# AddOnBoardArduinoRTC.net
KiCad netlist of a schematic drawn in EAGLE
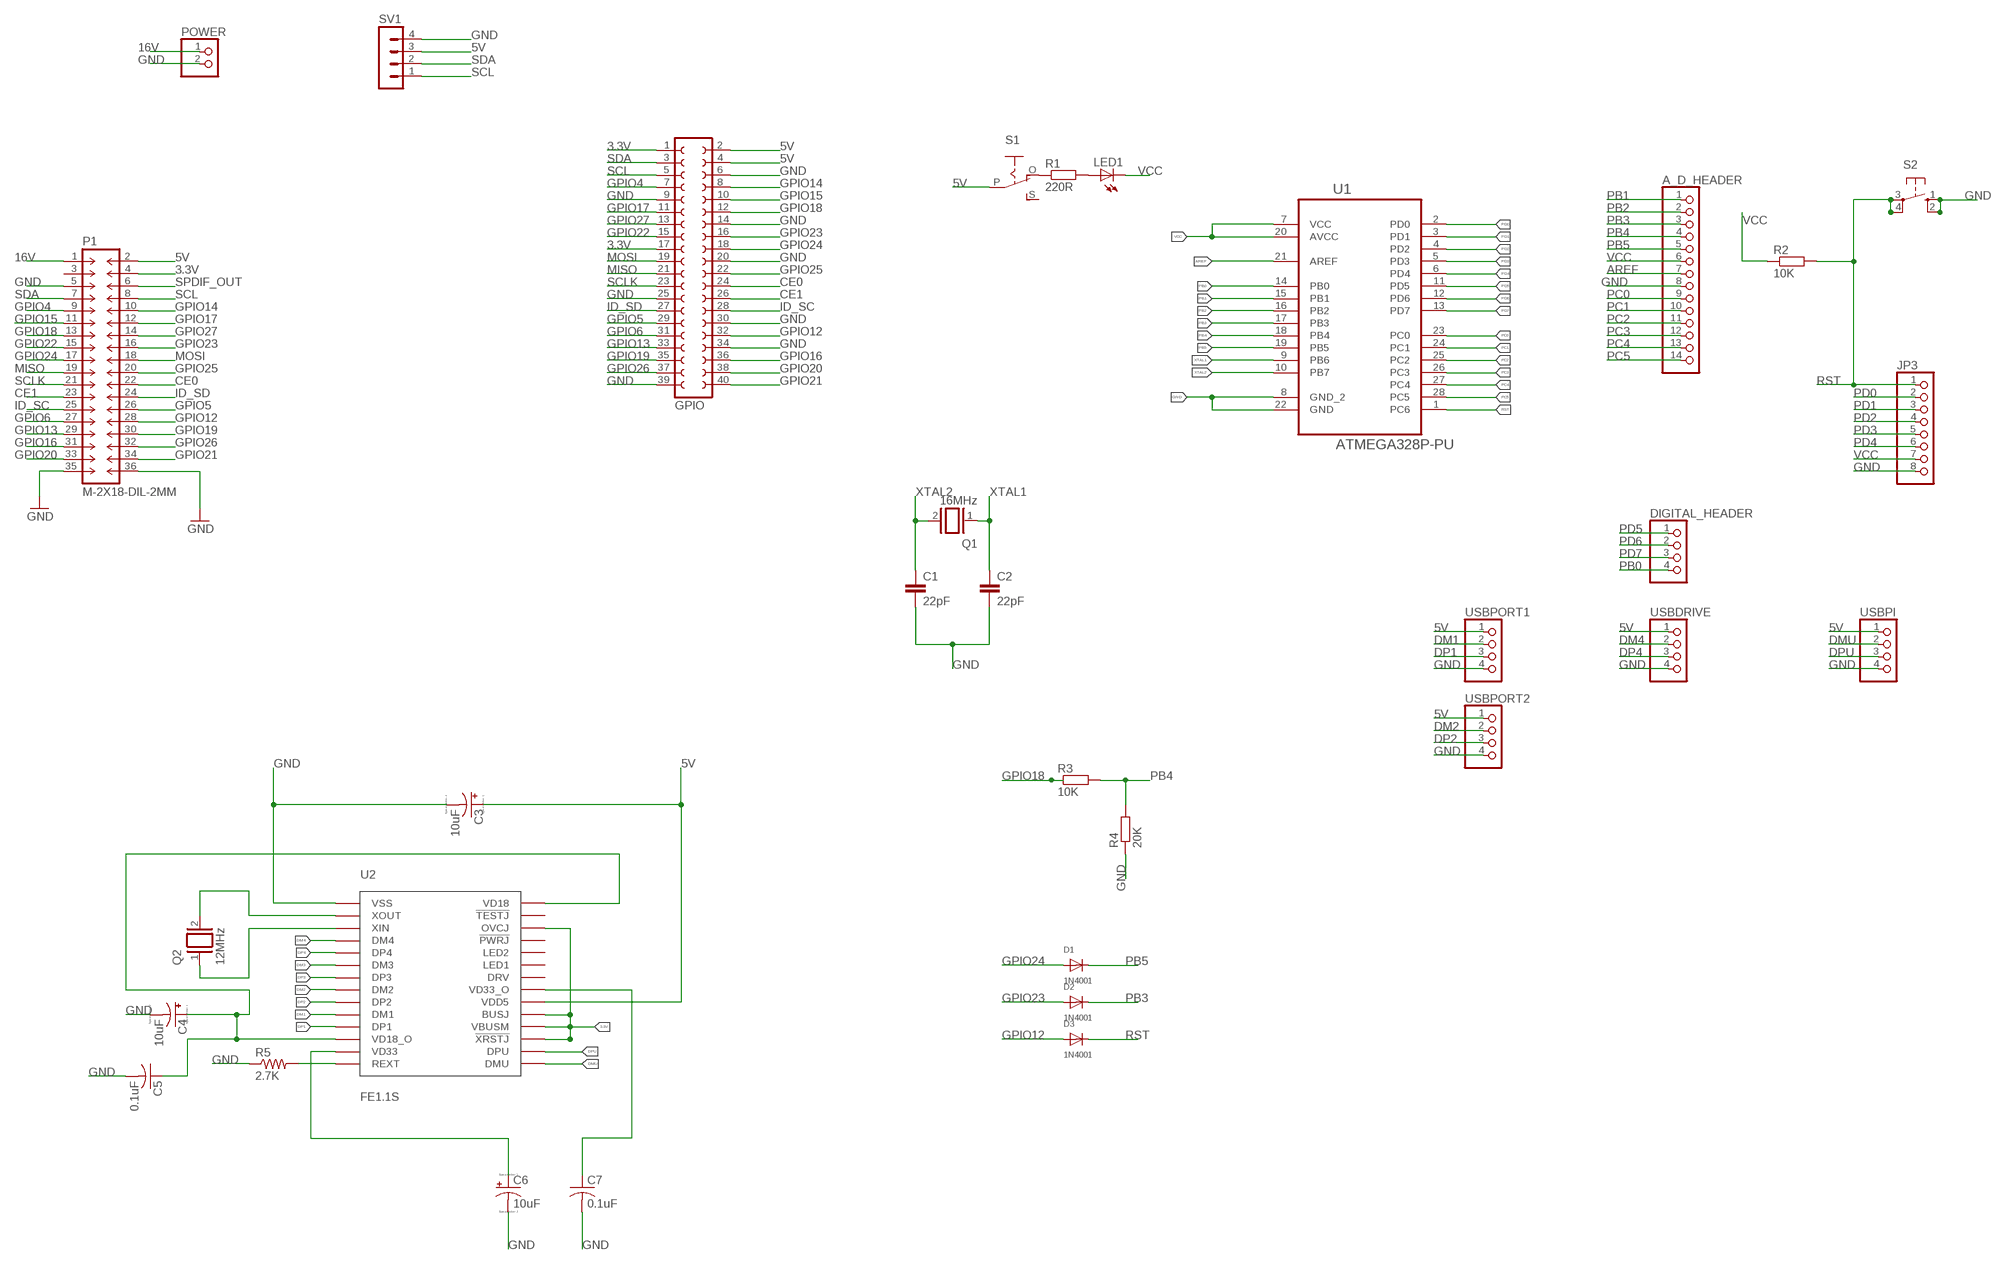
[diagram p0: schematic, sheet 1]

(export (version "E")
  (design (tool "Eeschema 10.0.6"))
  (components
    (comp (ref "A_D_HEADER")
      (value "PINHD-1X14")
      (footprint "eagle-import:1X14")
      (libsource (lib "eagle-import") (part "PINHD-1X14"))
    )
    (comp (ref "C1")
      (value "22pF")
      (footprint "eagle-import:C025-024X044")
      (libsource (lib "eagle-import") (part "C-EU025-024X044"))
    )
    (comp (ref "C2")
      (value "22pF")
      (footprint "eagle-import:C025-024X044")
      (libsource (lib "eagle-import") (part "C-EU025-024X044"))
    )
    (comp (ref "C3")
      (value "10uF")
      (footprint "eagle-import:153CLV-0605")
      (libsource (lib "eagle-import") (part "CPOL-US153CLV-0605"))
    )
    (comp (ref "C4")
      (value "10uF")
      (footprint "eagle-import:153CLV-0605")
      (libsource (lib "eagle-import") (part "CPOL-US153CLV-0605"))
    )
    (comp (ref "C5")
      (value "0.1uF")
      (footprint "eagle-import:C1206")
      (libsource (lib "eagle-import") (part "C-USC1206"))
    )
    (comp (ref "C6")
      (value "10uF")
      (footprint "eagle-import:153CLV-0605")
      (libsource (lib "eagle-import") (part "CPOL-US153CLV-0605"))
    )
    (comp (ref "C7")
      (value "0.1uF")
      (footprint "eagle-import:C1206")
      (libsource (lib "eagle-import") (part "C-USC1206"))
    )
    (comp (ref "D1")
      (value "1N4001")
      (footprint "eagle-import:SMADIODE")
      (libsource (lib "eagle-import") (part "DIODESMA"))
    )
    (comp (ref "D2")
      (value "1N4001")
      (footprint "eagle-import:SMADIODE")
      (libsource (lib "eagle-import") (part "DIODESMA"))
    )
    (comp (ref "D3")
      (value "1N4001")
      (footprint "eagle-import:SMADIODE")
      (libsource (lib "eagle-import") (part "DIODESMA"))
    )
    (comp (ref "DIGITAL_HEADER")
      (value "PINHD-1X4")
      (footprint "eagle-import:1X04")
      (libsource (lib "eagle-import") (part "PINHD-1X4"))
    )
    (comp (ref "GPIO")
      (value "FE20-2")
      (footprint "eagle-import:FE20-2")
      (libsource (lib "eagle-import") (part "FE20-2"))
    )
    (comp (ref "JP3")
      (value "PINHD-1X8")
      (footprint "eagle-import:1X08")
      (libsource (lib "eagle-import") (part "PINHD-1X8"))
    )
    (comp (ref "LED1")
      (value "LED5MM")
      (footprint "eagle-import:LED5MM")
      (libsource (lib "eagle-import") (part "LED5MM"))
    )
    (comp (ref "P1")
      (value "M-2X18-DIL-2MM")
      (footprint "eagle-import:DIL-2MM-2X18")
      (libsource (lib "eagle-import") (part "M-2X18-DIL-2MM"))
    )
    (comp (ref "POWER")
      (value "PINHD-1X2")
      (footprint "eagle-import:1X02")
      (libsource (lib "eagle-import") (part "PINHD-1X2"))
    )
    (comp (ref "Q1")
      (value "16MHz")
      (footprint "eagle-import:QS")
      (libsource (lib "eagle-import") (part "XTAL/S"))
    )
    (comp (ref "Q2")
      (value "12MHz")
      (footprint "eagle-import:QS")
      (libsource (lib "eagle-import") (part "XTAL/S"))
    )
    (comp (ref "R1")
      (value "220R")
      (footprint "eagle-import:M1206")
      (libsource (lib "eagle-import") (part "R-EU_M1206"))
    )
    (comp (ref "R2")
      (value "10K")
      (footprint "eagle-import:M1206")
      (libsource (lib "eagle-import") (part "R-EU_M1206"))
    )
    (comp (ref "R3")
      (value "10K")
      (footprint "eagle-import:M1206")
      (libsource (lib "eagle-import") (part "R-EU_M1206"))
    )
    (comp (ref "R4")
      (value "20K")
      (footprint "eagle-import:M1206")
      (libsource (lib "eagle-import") (part "R-EU_M1206"))
    )
    (comp (ref "R5")
      (value "2.7K")
      (footprint "eagle-import:M1206")
      (libsource (lib "eagle-import") (part "R-US_M1206"))
    )
    (comp (ref "S1")
      (value "EG1218S")
      (footprint "eagle-import:EG1218")
      (libsource (lib "eagle-import") (part "EG1218S"))
    )
    (comp (ref "S2")
      (value "10-XX")
      (footprint "eagle-import:B3F-10XX")
      (fields (field (name "MPN") "B3F-1000"))
      (libsource (lib "eagle-import") (part "10-XX"))
    )
    (comp (ref "SV1")
      (value "MA04-1")
      (footprint "eagle-import:MA04-1")
      (libsource (lib "eagle-import") (part "MA04-1"))
    )
    (comp (ref "U1")
      (value "ATMEGA328P-PU")
      (footprint "eagle-import:DIP254P762X457-28")
      (libsource (lib "eagle-import") (part "ATMEGA328P-PU"))
    )
    (comp (ref "U2")
      (value "FE1.1S")
      (footprint "eagle-import:SSOP-28")
      (libsource (lib "eagle-import") (part "FE1.1S"))
    )
    (comp (ref "USBDRIVE")
      (value "PINHD-1X4")
      (footprint "eagle-import:1X04")
      (libsource (lib "eagle-import") (part "PINHD-1X4"))
    )
    (comp (ref "USBPI")
      (value "PINHD-1X4")
      (footprint "eagle-import:1X04")
      (libsource (lib "eagle-import") (part "PINHD-1X4"))
    )
    (comp (ref "USBPORT1")
      (value "PINHD-1X4")
      (footprint "eagle-import:1X04")
      (libsource (lib "eagle-import") (part "PINHD-1X4"))
    )
    (comp (ref "USBPORT2")
      (value "PINHD-1X4")
      (footprint "eagle-import:1X04")
      (libsource (lib "eagle-import") (part "PINHD-1X4"))
    )
  )
  (nets
    (net (code "1") (name "/5V") (class "Default")
      (node (ref "C3") (pin "+") (pinfunction "+_+") (pintype "passive"))
      (node (ref "GPIO") (pin "2") (pinfunction "2_2") (pintype "passive"))
      (node (ref "GPIO") (pin "4") (pinfunction "4_4") (pintype "passive"))
      (node (ref "P1") (pin "2") (pinfunction "2_2") (pintype "passive"))
      (node (ref "S1") (pin "P") (pinfunction "P_P") (pintype "passive"))
      (node (ref "SV1") (pin "3") (pinfunction "3_3") (pintype "passive"))
      (node (ref "U2") (pin "20") (pinfunction "VDD5_20") (pintype "power_in"))
      (node (ref "USBDRIVE") (pin "1") (pinfunction "1_1") (pintype "passive"))
      (node (ref "USBPI") (pin "1") (pinfunction "1_1") (pintype "passive"))
      (node (ref "USBPORT1") (pin "1") (pinfunction "1_1") (pintype "passive"))
      (node (ref "USBPORT2") (pin "1") (pinfunction "1_1") (pintype "passive"))
    )
    (net (code "2") (name "/16V") (class "Default")
      (node (ref "P1") (pin "1") (pinfunction "1_1") (pintype "passive"))
      (node (ref "POWER") (pin "1") (pinfunction "1_1") (pintype "passive"))
    )
    (net (code "3") (name "/CE0") (class "Default")
      (node (ref "GPIO") (pin "24") (pinfunction "24_24") (pintype "passive"))
      (node (ref "P1") (pin "22") (pinfunction "22_22") (pintype "passive"))
    )
    (net (code "4") (name "/CE1") (class "Default")
      (node (ref "GPIO") (pin "26") (pinfunction "26_26") (pintype "passive"))
      (node (ref "P1") (pin "23") (pinfunction "23_23") (pintype "passive"))
    )
    (net (code "5") (name "/GPIO4") (class "Default")
      (node (ref "GPIO") (pin "7") (pinfunction "7_7") (pintype "passive"))
      (node (ref "P1") (pin "9") (pinfunction "9_9") (pintype "passive"))
    )
    (net (code "6") (name "/GPIO5") (class "Default")
      (node (ref "GPIO") (pin "29") (pinfunction "29_29") (pintype "passive"))
      (node (ref "P1") (pin "26") (pinfunction "26_26") (pintype "passive"))
    )
    (net (code "7") (name "/GPIO6") (class "Default")
      (node (ref "GPIO") (pin "31") (pinfunction "31_31") (pintype "passive"))
      (node (ref "P1") (pin "27") (pinfunction "27_27") (pintype "passive"))
    )
    (net (code "8") (name "/GPIO12") (class "Default")
      (node (ref "D3") (pin "A") (pinfunction "A_A") (pintype "passive"))
      (node (ref "GPIO") (pin "32") (pinfunction "32_32") (pintype "passive"))
      (node (ref "P1") (pin "28") (pinfunction "28_28") (pintype "passive"))
    )
    (net (code "9") (name "/GPIO13") (class "Default")
      (node (ref "GPIO") (pin "33") (pinfunction "33_33") (pintype "passive"))
      (node (ref "P1") (pin "29") (pinfunction "29_29") (pintype "passive"))
    )
    (net (code "10") (name "/GPIO14") (class "Default")
      (node (ref "GPIO") (pin "8") (pinfunction "8_8") (pintype "passive"))
      (node (ref "P1") (pin "10") (pinfunction "10_10") (pintype "passive"))
    )
    (net (code "11") (name "/GPIO15") (class "Default")
      (node (ref "GPIO") (pin "10") (pinfunction "10_10") (pintype "passive"))
      (node (ref "P1") (pin "11") (pinfunction "11_11") (pintype "passive"))
    )
    (net (code "12") (name "/GPIO16") (class "Default")
      (node (ref "GPIO") (pin "36") (pinfunction "36_36") (pintype "passive"))
      (node (ref "P1") (pin "31") (pinfunction "31_31") (pintype "passive"))
    )
    (net (code "13") (name "/GPIO17") (class "Default")
      (node (ref "GPIO") (pin "11") (pinfunction "11_11") (pintype "passive"))
      (node (ref "P1") (pin "12") (pinfunction "12_12") (pintype "passive"))
    )
    (net (code "14") (name "/GPIO18") (class "Default")
      (node (ref "GPIO") (pin "12") (pinfunction "12_12") (pintype "passive"))
      (node (ref "P1") (pin "13") (pinfunction "13_13") (pintype "passive"))
      (node (ref "R3") (pin "1") (pinfunction "1_1") (pintype "passive"))
    )
    (net (code "15") (name "/GPIO19") (class "Default")
      (node (ref "GPIO") (pin "35") (pinfunction "35_35") (pintype "passive"))
      (node (ref "P1") (pin "30") (pinfunction "30_30") (pintype "passive"))
    )
    (net (code "16") (name "/GPIO20") (class "Default")
      (node (ref "GPIO") (pin "38") (pinfunction "38_38") (pintype "passive"))
      (node (ref "P1") (pin "33") (pinfunction "33_33") (pintype "passive"))
    )
    (net (code "17") (name "/GPIO21") (class "Default")
      (node (ref "GPIO") (pin "40") (pinfunction "40_40") (pintype "passive"))
      (node (ref "P1") (pin "34") (pinfunction "34_34") (pintype "passive"))
    )
    (net (code "18") (name "/GPIO22") (class "Default")
      (node (ref "GPIO") (pin "15") (pinfunction "15_15") (pintype "passive"))
      (node (ref "P1") (pin "15") (pinfunction "15_15") (pintype "passive"))
    )
    (net (code "19") (name "/GPIO23") (class "Default")
      (node (ref "D2") (pin "A") (pinfunction "A_A") (pintype "passive"))
      (node (ref "GPIO") (pin "16") (pinfunction "16_16") (pintype "passive"))
      (node (ref "P1") (pin "16") (pinfunction "16_16") (pintype "passive"))
    )
    (net (code "20") (name "/GPIO24") (class "Default")
      (node (ref "D1") (pin "A") (pinfunction "A_A") (pintype "passive"))
      (node (ref "GPIO") (pin "18") (pinfunction "18_18") (pintype "passive"))
      (node (ref "P1") (pin "17") (pinfunction "17_17") (pintype "passive"))
    )
    (net (code "21") (name "/GPIO25") (class "Default")
      (node (ref "GPIO") (pin "22") (pinfunction "22_22") (pintype "passive"))
      (node (ref "P1") (pin "20") (pinfunction "20_20") (pintype "passive"))
    )
    (net (code "22") (name "/GPIO26") (class "Default")
      (node (ref "GPIO") (pin "37") (pinfunction "37_37") (pintype "passive"))
      (node (ref "P1") (pin "32") (pinfunction "32_32") (pintype "passive"))
    )
    (net (code "23") (name "/GPIO27") (class "Default")
      (node (ref "GPIO") (pin "13") (pinfunction "13_13") (pintype "passive"))
      (node (ref "P1") (pin "14") (pinfunction "14_14") (pintype "passive"))
    )
    (net (code "24") (name "/ID_SC") (class "Default")
      (node (ref "GPIO") (pin "28") (pinfunction "28_28") (pintype "passive"))
      (node (ref "P1") (pin "25") (pinfunction "25_25") (pintype "passive"))
    )
    (net (code "25") (name "/ID_SD") (class "Default")
      (node (ref "GPIO") (pin "27") (pinfunction "27_27") (pintype "passive"))
      (node (ref "P1") (pin "24") (pinfunction "24_24") (pintype "passive"))
    )
    (net (code "26") (name "/MISO") (class "Default")
      (node (ref "GPIO") (pin "21") (pinfunction "21_21") (pintype "passive"))
      (node (ref "P1") (pin "19") (pinfunction "19_19") (pintype "passive"))
    )
    (net (code "27") (name "/MOSI") (class "Default")
      (node (ref "GPIO") (pin "19") (pinfunction "19_19") (pintype "passive"))
      (node (ref "P1") (pin "18") (pinfunction "18_18") (pintype "passive"))
    )
    (net (code "28") (name "/SCL") (class "Default")
      (node (ref "GPIO") (pin "5") (pinfunction "5_5") (pintype "passive"))
      (node (ref "P1") (pin "8") (pinfunction "8_8") (pintype "passive"))
      (node (ref "SV1") (pin "1") (pinfunction "1_1") (pintype "passive"))
    )
    (net (code "29") (name "/SCLK") (class "Default")
      (node (ref "GPIO") (pin "23") (pinfunction "23_23") (pintype "passive"))
      (node (ref "P1") (pin "21") (pinfunction "21_21") (pintype "passive"))
    )
    (net (code "30") (name "/SDA") (class "Default")
      (node (ref "GPIO") (pin "3") (pinfunction "3_3") (pintype "passive"))
      (node (ref "P1") (pin "7") (pinfunction "7_7") (pintype "passive"))
      (node (ref "SV1") (pin "2") (pinfunction "2_2") (pintype "passive"))
    )
    (net (code "31") (name "/SPDIF_OUT") (class "Default")
      (node (ref "P1") (pin "6") (pinfunction "6_6") (pintype "passive"))
    )
    (net (code "32") (name "3.3V") (class "Default")
      (node (ref "GPIO") (pin "1") (pinfunction "1_1") (pintype "passive"))
      (node (ref "GPIO") (pin "17") (pinfunction "17_17") (pintype "passive"))
      (node (ref "P1") (pin "4") (pinfunction "4_4") (pintype "passive"))
      (node (ref "U2") (pin "17") (pinfunction "~{XRSTJ}_17") (pintype "input"))
      (node (ref "U2") (pin "18") (pinfunction "VBUSM_18") (pintype "input"))
      (node (ref "U2") (pin "19") (pinfunction "BUSJ_19") (pintype "input"))
      (node (ref "U2") (pin "26") (pinfunction "OVCJ_26") (pintype "input"))
    )
    (net (code "33") (name "AREF") (class "Default")
      (node (ref "A_D_HEADER") (pin "7") (pinfunction "7_7") (pintype "passive"))
      (node (ref "U1") (pin "21") (pinfunction "AREF_21") (pintype "input"))
    )
    (net (code "34") (name "DM1") (class "Default")
      (node (ref "U2") (pin "10") (pinfunction "DM1_10") (pintype "bidirectional"))
      (node (ref "USBPORT1") (pin "2") (pinfunction "2_2") (pintype "passive"))
    )
    (net (code "35") (name "DM2") (class "Default")
      (node (ref "U2") (pin "8") (pinfunction "DM2_8") (pintype "bidirectional"))
      (node (ref "USBPORT2") (pin "2") (pinfunction "2_2") (pintype "passive"))
    )
    (net (code "36") (name "DM3") (class "Default")
      (node (ref "U2") (pin "6") (pinfunction "DM3_6") (pintype "bidirectional"))
    )
    (net (code "37") (name "DM4") (class "Default")
      (node (ref "U2") (pin "4") (pinfunction "DM4_4") (pintype "bidirectional"))
      (node (ref "USBDRIVE") (pin "2") (pinfunction "2_2") (pintype "passive"))
    )
    (net (code "38") (name "DMU") (class "Default")
      (node (ref "U2") (pin "15") (pinfunction "DMU_15") (pintype "bidirectional"))
      (node (ref "USBPI") (pin "2") (pinfunction "2_2") (pintype "passive"))
    )
    (net (code "39") (name "DP1") (class "Default")
      (node (ref "U2") (pin "11") (pinfunction "DP1_11") (pintype "bidirectional"))
      (node (ref "USBPORT1") (pin "3") (pinfunction "3_3") (pintype "passive"))
    )
    (net (code "40") (name "DP2") (class "Default")
      (node (ref "U2") (pin "9") (pinfunction "DP2_9") (pintype "bidirectional"))
      (node (ref "USBPORT2") (pin "3") (pinfunction "3_3") (pintype "passive"))
    )
    (net (code "41") (name "DP3") (class "Default")
      (node (ref "U2") (pin "7") (pinfunction "DP3_7") (pintype "bidirectional"))
    )
    (net (code "42") (name "DP4") (class "Default")
      (node (ref "U2") (pin "5") (pinfunction "DP4_5") (pintype "bidirectional"))
      (node (ref "USBDRIVE") (pin "3") (pinfunction "3_3") (pintype "passive"))
    )
    (net (code "43") (name "DPU") (class "Default")
      (node (ref "U2") (pin "16") (pinfunction "DPU_16") (pintype "bidirectional"))
      (node (ref "USBPI") (pin "3") (pinfunction "3_3") (pintype "passive"))
    )
    (net (code "44") (name "GND") (class "Default")
      (node (ref "A_D_HEADER") (pin "8") (pinfunction "8_8") (pintype "passive"))
      (node (ref "C1") (pin "2") (pinfunction "2_2") (pintype "passive"))
      (node (ref "C2") (pin "2") (pinfunction "2_2") (pintype "passive"))
      (node (ref "C3") (pin "-") (pinfunction "-_-") (pintype "passive"))
      (node (ref "C4") (pin "-") (pinfunction "-_-") (pintype "passive"))
      (node (ref "C5") (pin "2") (pinfunction "2_2") (pintype "passive"))
      (node (ref "C6") (pin "-") (pinfunction "-_-") (pintype "passive"))
      (node (ref "C7") (pin "2") (pinfunction "2_2") (pintype "passive"))
      (node (ref "GPIO") (pin "14") (pinfunction "14_14") (pintype "passive"))
      (node (ref "GPIO") (pin "20") (pinfunction "20_20") (pintype "passive"))
      (node (ref "GPIO") (pin "25") (pinfunction "25_25") (pintype "passive"))
      (node (ref "GPIO") (pin "30") (pinfunction "30_30") (pintype "passive"))
      (node (ref "GPIO") (pin "34") (pinfunction "34_34") (pintype "passive"))
      (node (ref "GPIO") (pin "39") (pinfunction "39_39") (pintype "passive"))
      (node (ref "GPIO") (pin "6") (pinfunction "6_6") (pintype "passive"))
      (node (ref "GPIO") (pin "9") (pinfunction "9_9") (pintype "passive"))
      (node (ref "JP3") (pin "8") (pinfunction "8_8") (pintype "passive"))
      (node (ref "P1") (pin "35") (pinfunction "35_35") (pintype "passive"))
      (node (ref "P1") (pin "36") (pinfunction "36_36") (pintype "passive"))
      (node (ref "P1") (pin "5") (pinfunction "5_5") (pintype "passive"))
      (node (ref "POWER") (pin "2") (pinfunction "2_2") (pintype "passive"))
      (node (ref "R4") (pin "1") (pinfunction "1_1") (pintype "passive"))
      (node (ref "R5") (pin "1") (pinfunction "1_1") (pintype "passive"))
      (node (ref "S2") (pin "1") (pinfunction "S_1") (pintype "passive"))
      (node (ref "S2") (pin "2") (pinfunction "S1_2") (pintype "passive"))
      (node (ref "SV1") (pin "4") (pinfunction "4_4") (pintype "passive"))
      (node (ref "U1") (pin "22") (pinfunction "GND_22") (pintype "passive"))
      (node (ref "U1") (pin "8") (pinfunction "GND_2_8") (pintype "passive"))
      (node (ref "U2") (pin "1") (pinfunction "VSS_1") (pintype "power_in"))
      (node (ref "USBDRIVE") (pin "4") (pinfunction "4_4") (pintype "passive"))
      (node (ref "USBPI") (pin "4") (pinfunction "4_4") (pintype "passive"))
      (node (ref "USBPORT1") (pin "4") (pinfunction "4_4") (pintype "passive"))
      (node (ref "USBPORT2") (pin "4") (pinfunction "4_4") (pintype "passive"))
    )
    (net (code "45") (name "Net-(LED1-PadA)") (class "Default")
      (node (ref "LED1") (pin "A") (pinfunction "A_A") (pintype "passive"))
      (node (ref "R1") (pin "2") (pinfunction "2_2") (pintype "passive"))
    )
    (net (code "46") (name "Net-(R1-Pad1)") (class "Default")
      (node (ref "R1") (pin "1") (pinfunction "1_1") (pintype "passive"))
      (node (ref "S1") (pin "O") (pinfunction "O_O") (pintype "passive"))
    )
    (net (code "47") (name "Net-(U2-REXT)") (class "Default")
      (node (ref "R5") (pin "2") (pinfunction "2_2") (pintype "passive"))
      (node (ref "U2") (pin "14") (pinfunction "REXT_14") (pintype "bidirectional"))
    )
    (net (code "48") (name "Net-(U2-VD18)") (class "Default")
      (node (ref "C4") (pin "+") (pinfunction "+_+") (pintype "passive"))
      (node (ref "C5") (pin "1") (pinfunction "1_1") (pintype "passive"))
      (node (ref "U2") (pin "12") (pinfunction "VD18_O_12") (pintype "power_in"))
      (node (ref "U2") (pin "28") (pinfunction "VD18_28") (pintype "power_in"))
    )
    (net (code "49") (name "Net-(U2-VD33)") (class "Default")
      (node (ref "C6") (pin "+") (pinfunction "+_+") (pintype "passive"))
      (node (ref "U2") (pin "13") (pinfunction "VD33_13") (pintype "power_in"))
    )
    (net (code "50") (name "Net-(U2-VD33_O)") (class "Default")
      (node (ref "C7") (pin "1") (pinfunction "1_1") (pintype "passive"))
      (node (ref "U2") (pin "21") (pinfunction "VD33_O_21") (pintype "power_in"))
    )
    (net (code "51") (name "Net-(U2-XIN)") (class "Default")
      (node (ref "Q2") (pin "1") (pinfunction "1_1") (pintype "passive"))
      (node (ref "U2") (pin "3") (pinfunction "XIN_3") (pintype "input"))
    )
    (net (code "52") (name "Net-(U2-XOUT)") (class "Default")
      (node (ref "Q2") (pin "2") (pinfunction "2_2") (pintype "passive"))
      (node (ref "U2") (pin "2") (pinfunction "XOUT_2") (pintype "output"))
    )
    (net (code "53") (name "PB0") (class "Default")
      (node (ref "DIGITAL_HEADER") (pin "4") (pinfunction "4_4") (pintype "passive"))
      (node (ref "U1") (pin "14") (pinfunction "PB0_14") (pintype "bidirectional"))
    )
    (net (code "54") (name "PB1") (class "Default")
      (node (ref "A_D_HEADER") (pin "1") (pinfunction "1_1") (pintype "passive"))
      (node (ref "U1") (pin "15") (pinfunction "PB1_15") (pintype "bidirectional"))
    )
    (net (code "55") (name "PB2") (class "Default")
      (node (ref "A_D_HEADER") (pin "2") (pinfunction "2_2") (pintype "passive"))
      (node (ref "U1") (pin "16") (pinfunction "PB2_16") (pintype "bidirectional"))
    )
    (net (code "56") (name "PB3") (class "Default")
      (node (ref "A_D_HEADER") (pin "3") (pinfunction "3_3") (pintype "passive"))
      (node (ref "D2") (pin "C") (pinfunction "C_C") (pintype "passive"))
      (node (ref "U1") (pin "17") (pinfunction "PB3_17") (pintype "bidirectional"))
    )
    (net (code "57") (name "PB4") (class "Default")
      (node (ref "A_D_HEADER") (pin "4") (pinfunction "4_4") (pintype "passive"))
      (node (ref "R3") (pin "2") (pinfunction "2_2") (pintype "passive"))
      (node (ref "R4") (pin "2") (pinfunction "2_2") (pintype "passive"))
      (node (ref "U1") (pin "18") (pinfunction "PB4_18") (pintype "bidirectional"))
    )
    (net (code "58") (name "PB5") (class "Default")
      (node (ref "A_D_HEADER") (pin "5") (pinfunction "5_5") (pintype "passive"))
      (node (ref "D1") (pin "C") (pinfunction "C_C") (pintype "passive"))
      (node (ref "U1") (pin "19") (pinfunction "PB5_19") (pintype "bidirectional"))
    )
    (net (code "59") (name "PC0") (class "Default")
      (node (ref "A_D_HEADER") (pin "9") (pinfunction "9_9") (pintype "passive"))
      (node (ref "U1") (pin "23") (pinfunction "PC0_23") (pintype "bidirectional"))
    )
    (net (code "60") (name "PC1") (class "Default")
      (node (ref "A_D_HEADER") (pin "10") (pinfunction "10_10") (pintype "passive"))
      (node (ref "U1") (pin "24") (pinfunction "PC1_24") (pintype "bidirectional"))
    )
    (net (code "61") (name "PC2") (class "Default")
      (node (ref "A_D_HEADER") (pin "11") (pinfunction "11_11") (pintype "passive"))
      (node (ref "U1") (pin "25") (pinfunction "PC2_25") (pintype "bidirectional"))
    )
    (net (code "62") (name "PC3") (class "Default")
      (node (ref "A_D_HEADER") (pin "12") (pinfunction "12_12") (pintype "passive"))
      (node (ref "U1") (pin "26") (pinfunction "PC3_26") (pintype "bidirectional"))
    )
    (net (code "63") (name "PC4") (class "Default")
      (node (ref "A_D_HEADER") (pin "13") (pinfunction "13_13") (pintype "passive"))
      (node (ref "U1") (pin "27") (pinfunction "PC4_27") (pintype "bidirectional"))
    )
    (net (code "64") (name "PC5") (class "Default")
      (node (ref "A_D_HEADER") (pin "14") (pinfunction "14_14") (pintype "passive"))
      (node (ref "U1") (pin "28") (pinfunction "PC5_28") (pintype "bidirectional"))
    )
    (net (code "65") (name "PD0") (class "Default")
      (node (ref "JP3") (pin "2") (pinfunction "2_2") (pintype "passive"))
      (node (ref "U1") (pin "2") (pinfunction "PD0_2") (pintype "bidirectional"))
    )
    (net (code "66") (name "PD1") (class "Default")
      (node (ref "JP3") (pin "3") (pinfunction "3_3") (pintype "passive"))
      (node (ref "U1") (pin "3") (pinfunction "PD1_3") (pintype "bidirectional"))
    )
    (net (code "67") (name "PD2") (class "Default")
      (node (ref "JP3") (pin "4") (pinfunction "4_4") (pintype "passive"))
      (node (ref "U1") (pin "4") (pinfunction "PD2_4") (pintype "bidirectional"))
    )
    (net (code "68") (name "PD3") (class "Default")
      (node (ref "JP3") (pin "5") (pinfunction "5_5") (pintype "passive"))
      (node (ref "U1") (pin "5") (pinfunction "PD3_5") (pintype "bidirectional"))
    )
    (net (code "69") (name "PD4") (class "Default")
      (node (ref "JP3") (pin "6") (pinfunction "6_6") (pintype "passive"))
      (node (ref "U1") (pin "6") (pinfunction "PD4_6") (pintype "bidirectional"))
    )
    (net (code "70") (name "PD5") (class "Default")
      (node (ref "DIGITAL_HEADER") (pin "1") (pinfunction "1_1") (pintype "passive"))
      (node (ref "U1") (pin "11") (pinfunction "PD5_11") (pintype "bidirectional"))
    )
    (net (code "71") (name "PD6") (class "Default")
      (node (ref "DIGITAL_HEADER") (pin "2") (pinfunction "2_2") (pintype "passive"))
      (node (ref "U1") (pin "12") (pinfunction "PD6_12") (pintype "bidirectional"))
    )
    (net (code "72") (name "PD7") (class "Default")
      (node (ref "DIGITAL_HEADER") (pin "3") (pinfunction "3_3") (pintype "passive"))
      (node (ref "U1") (pin "13") (pinfunction "PD7_13") (pintype "bidirectional"))
    )
    (net (code "73") (name "RST") (class "Default")
      (node (ref "D3") (pin "C") (pinfunction "C_C") (pintype "passive"))
      (node (ref "JP3") (pin "1") (pinfunction "1_1") (pintype "passive"))
      (node (ref "R2") (pin "2") (pinfunction "2_2") (pintype "passive"))
      (node (ref "S2") (pin "3") (pinfunction "P_3") (pintype "passive"))
      (node (ref "S2") (pin "4") (pinfunction "P1_4") (pintype "passive"))
      (node (ref "U1") (pin "1") (pinfunction "PC6_1") (pintype "bidirectional"))
    )
    (net (code "74") (name "VCC") (class "Default")
      (node (ref "A_D_HEADER") (pin "6") (pinfunction "6_6") (pintype "passive"))
      (node (ref "JP3") (pin "7") (pinfunction "7_7") (pintype "passive"))
      (node (ref "LED1") (pin "K") (pinfunction "C_K") (pintype "passive"))
      (node (ref "R2") (pin "1") (pinfunction "1_1") (pintype "passive"))
      (node (ref "U1") (pin "20") (pinfunction "AVCC_20") (pintype "power_in"))
      (node (ref "U1") (pin "7") (pinfunction "VCC_7") (pintype "power_in"))
    )
    (net (code "75") (name "XTAL1") (class "Default")
      (node (ref "C2") (pin "1") (pinfunction "1_1") (pintype "passive"))
      (node (ref "Q1") (pin "1") (pinfunction "1_1") (pintype "passive"))
      (node (ref "U1") (pin "9") (pinfunction "PB6_9") (pintype "bidirectional"))
    )
    (net (code "76") (name "XTAL2") (class "Default")
      (node (ref "C1") (pin "1") (pinfunction "1_1") (pintype "passive"))
      (node (ref "Q1") (pin "2") (pinfunction "2_2") (pintype "passive"))
      (node (ref "U1") (pin "10") (pinfunction "PB7_10") (pintype "bidirectional"))
    )
    (net (code "77") (name "unconnected-(P1-Pad3)") (class "Default")
      (node (ref "P1") (pin "3") (pinfunction "3_3") (pintype "passive"))
    )
    (net (code "78") (name "unconnected-(S1-PadS)") (class "Default")
      (node (ref "S1") (pin "S") (pinfunction "S_S") (pintype "passive"))
    )
    (net (code "79") (name "unconnected-(U2-DRV-Pad22)") (class "Default")
      (node (ref "U2") (pin "22") (pinfunction "DRV_22") (pintype "bidirectional"))
    )
    (net (code "80") (name "unconnected-(U2-LED1-Pad23)") (class "Default")
      (node (ref "U2") (pin "23") (pinfunction "LED1_23") (pintype "bidirectional"))
    )
    (net (code "81") (name "unconnected-(U2-LED2-Pad24)") (class "Default")
      (node (ref "U2") (pin "24") (pinfunction "LED2_24") (pintype "bidirectional"))
    )
    (net (code "82") (name "unconnected-(U2-~{PWRJ}-Pad25)") (class "Default")
      (node (ref "U2") (pin "25") (pinfunction "~{PWRJ}_25") (pintype "output"))
    )
    (net (code "83") (name "unconnected-(U2-~{TESTJ}-Pad27)") (class "Default")
      (node (ref "U2") (pin "27") (pinfunction "~{TESTJ}_27") (pintype "bidirectional"))
    )
  )
)
